# 12usb.net
KiCad netlist of a schematic drawn in EasyEDA Pro
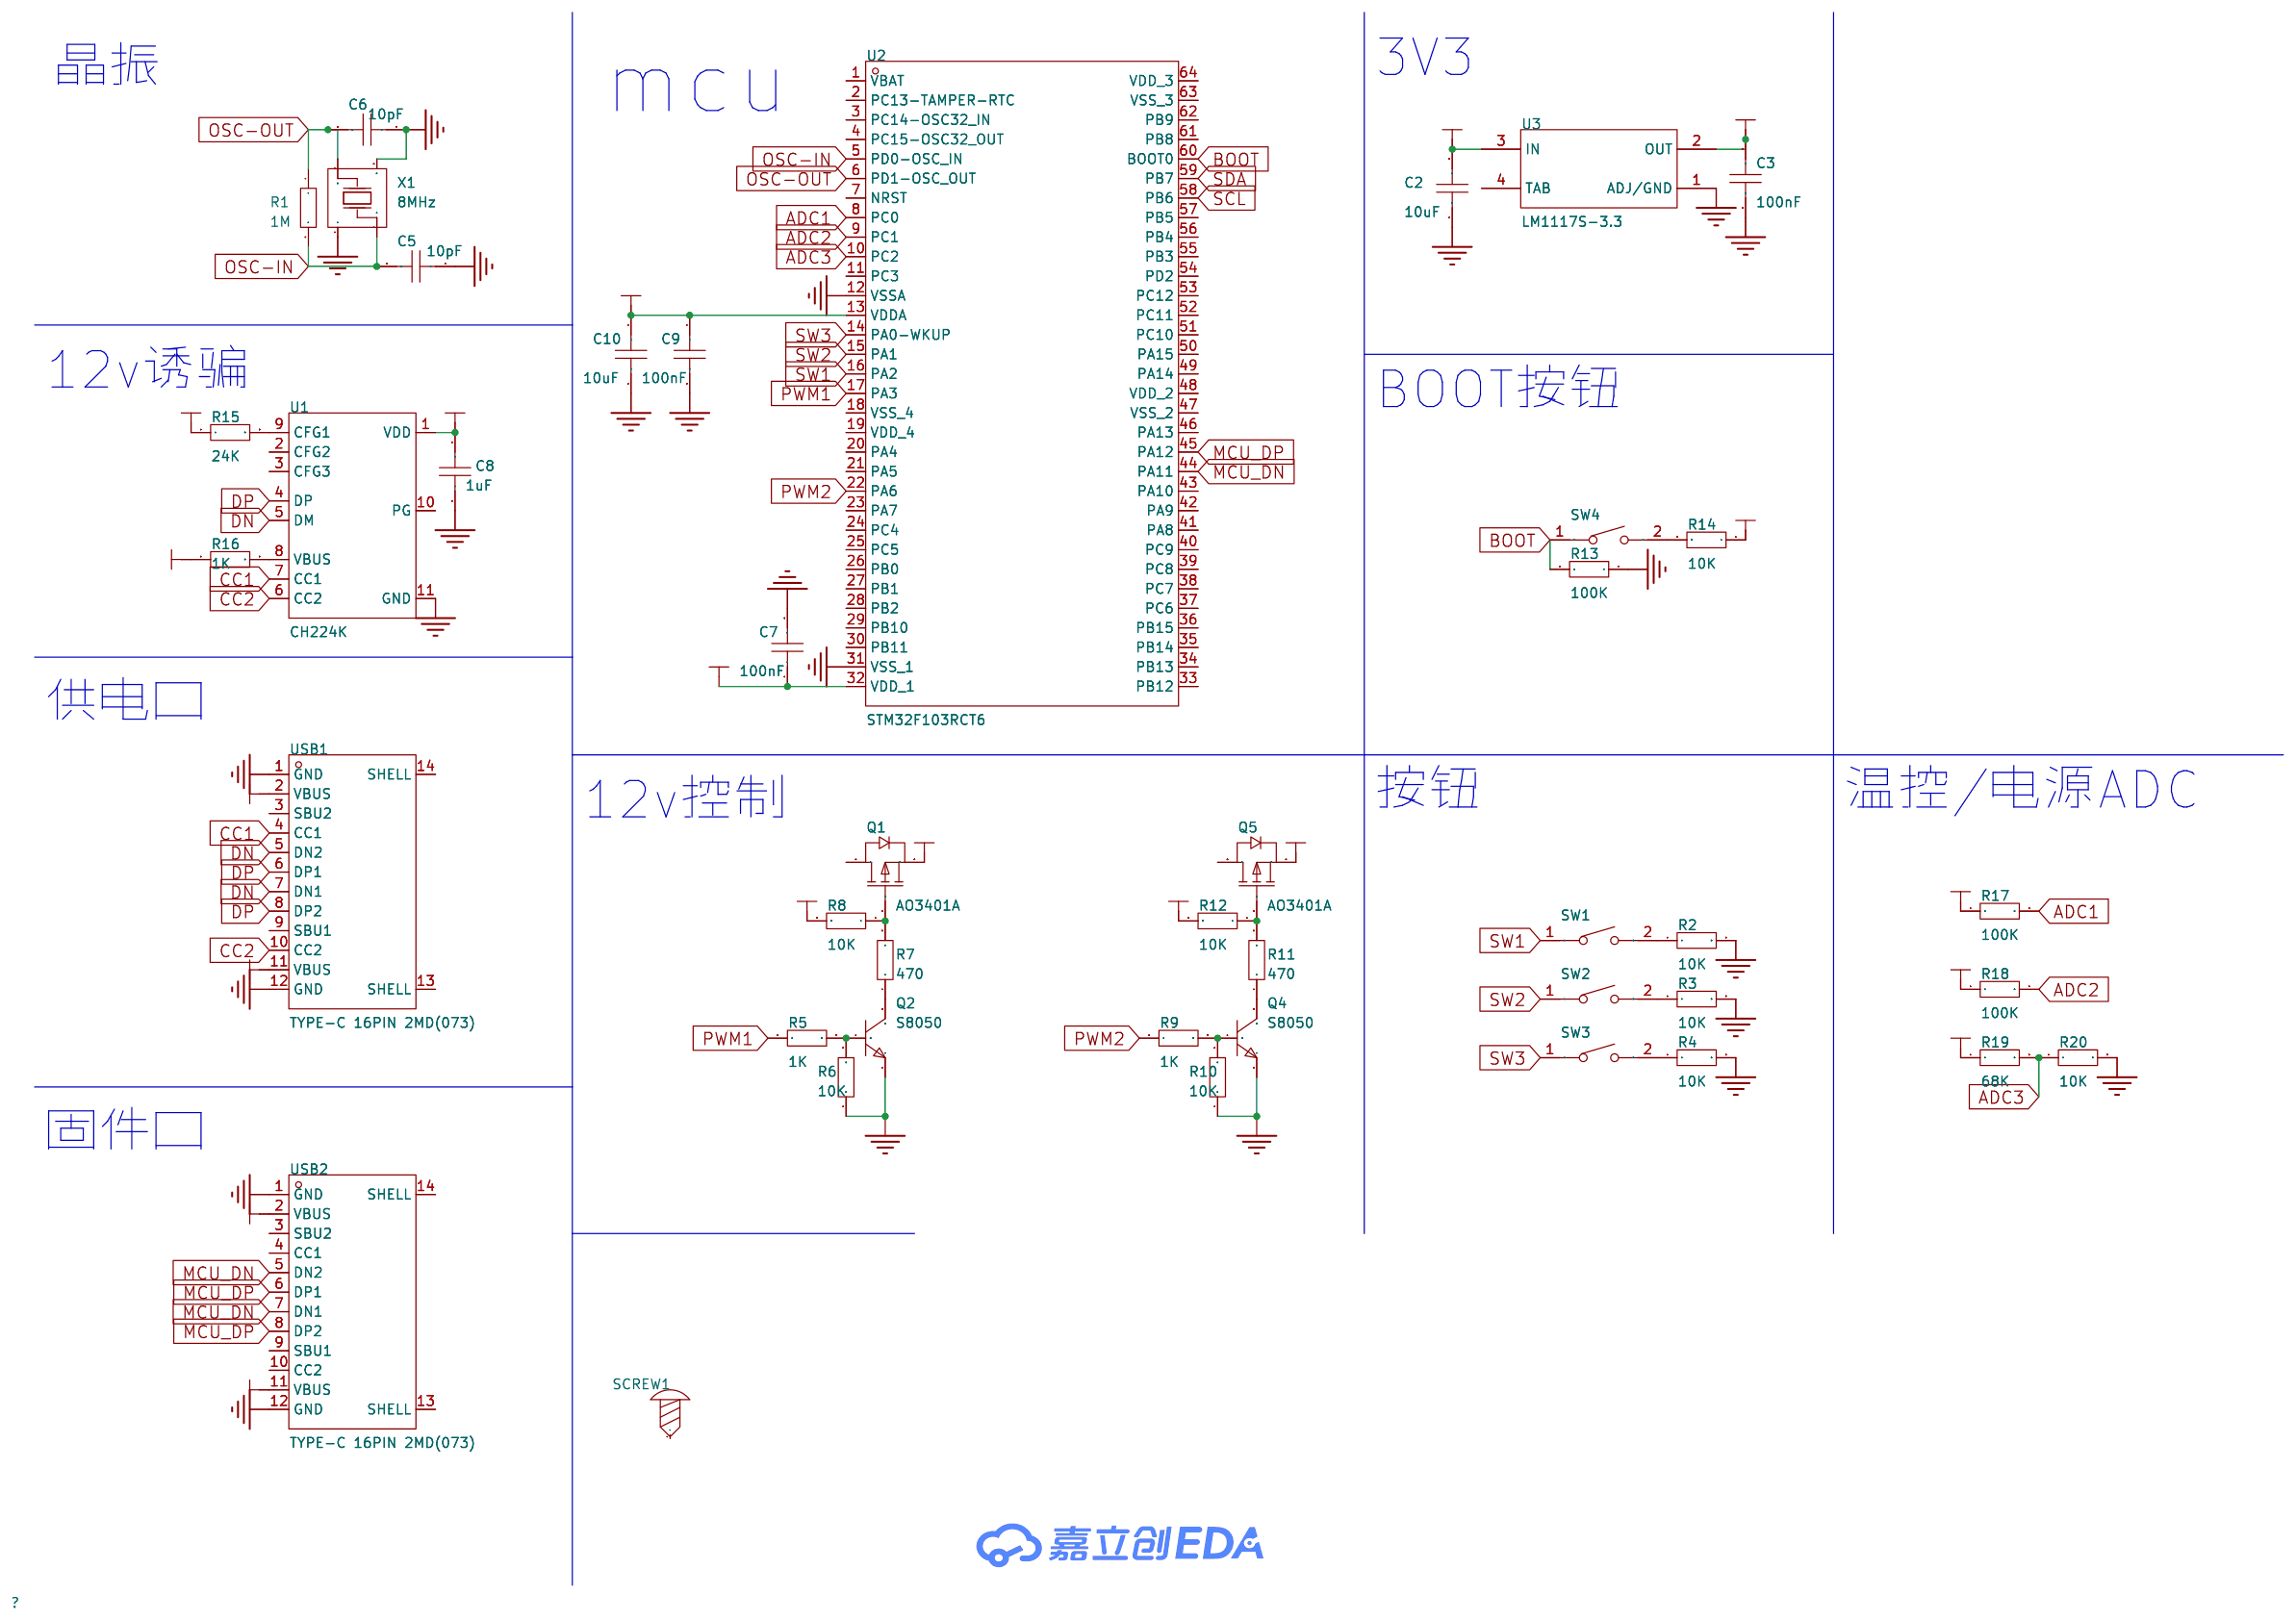
[diagram p0: schematic sheet]

(export (version "E")
  (design (tool "Eeschema 10.0.6"))
  (components
    (comp (ref "C2")
      (value "10uF")
      (footprint "easyedapro:C0603")
      (libsource (lib "easyedapro") (part "CapAcitance"))
    )
    (comp (ref "C3")
      (value "100nF")
      (footprint "easyedapro:C0603")
      (libsource (lib "easyedapro") (part "CapAcitance"))
    )
    (comp (ref "C5")
      (value "10pF")
      (footprint "easyedapro:C0603")
      (libsource (lib "easyedapro") (part "CapAcitance"))
    )
    (comp (ref "C6")
      (value "10pF")
      (footprint "easyedapro:C0603")
      (libsource (lib "easyedapro") (part "CapAcitance"))
    )
    (comp (ref "C7")
      (value "100nF")
      (footprint "easyedapro:C0603")
      (libsource (lib "easyedapro") (part "CapAcitance"))
    )
    (comp (ref "C8")
      (value "1uF")
      (footprint "easyedapro:C0603")
      (libsource (lib "easyedapro") (part "CapAcitance"))
    )
    (comp (ref "C9")
      (value "100nF")
      (footprint "easyedapro:C0603")
      (libsource (lib "easyedapro") (part "CapAcitance"))
    )
    (comp (ref "C10")
      (value "10uF")
      (footprint "easyedapro:C0603")
      (libsource (lib "easyedapro") (part "CapAcitance"))
    )
    (comp (ref "Q1")
      (value "AO3401A")
      (footprint "easyedapro:SOT-23_L2.9-W1.3-P1.90-LS2.4-BR")
      (fields (field (name "Manufacturer") "AOS"))
      (libsource (lib "easyedapro") (part "AO3401A"))
    )
    (comp (ref "Q2")
      (value "S8050")
      (footprint "easyedapro:SOT-23-3_L2.9-W1.3-P1.90-LS2.3-BR")
      (description "晶体管类型:NPN;集电极电流(Ic):500mA;集射极击穿电压(Vceo):25V;功率(Pd):300mW;直流电流增益(hFE@Ic,Vce):120@50mA,1.0V;")
      (fields (field (name "Manufacturer") "宏迦橙"))
      (libsource (lib "easyedapro") (part "S8050_C20069125"))
    )
    (comp (ref "Q4")
      (value "S8050")
      (footprint "easyedapro:SOT-23-3_L2.9-W1.3-P1.90-LS2.3-BR")
      (description "晶体管类型:NPN;集电极电流(Ic):500mA;集射极击穿电压(Vceo):25V;功率(Pd):300mW;直流电流增益(hFE@Ic,Vce):120@50mA,1.0V;")
      (fields (field (name "Manufacturer") "宏迦橙"))
      (libsource (lib "easyedapro") (part "S8050_C20069125"))
    )
    (comp (ref "Q5")
      (value "AO3401A")
      (footprint "easyedapro:SOT-23_L2.9-W1.3-P1.90-LS2.4-BR")
      (fields (field (name "Manufacturer") "AOS"))
      (libsource (lib "easyedapro") (part "AO3401A"))
    )
    (comp (ref "R1") (value "1M") (footprint "easyedapro:R0603") (libsource (lib "easyedapro") (part "电阻")))
    (comp (ref "R2") (value "10K") (footprint "easyedapro:R0603") (libsource (lib "easyedapro") (part "电阻")))
    (comp (ref "R3") (value "10K") (footprint "easyedapro:R0603") (libsource (lib "easyedapro") (part "电阻")))
    (comp (ref "R4") (value "10K") (footprint "easyedapro:R0603") (libsource (lib "easyedapro") (part "电阻")))
    (comp (ref "R5") (value "1K") (footprint "easyedapro:R0603") (libsource (lib "easyedapro") (part "电阻")))
    (comp (ref "R6") (value "10K") (footprint "easyedapro:R0603") (libsource (lib "easyedapro") (part "电阻")))
    (comp (ref "R7") (value "470") (footprint "easyedapro:R0603") (libsource (lib "easyedapro") (part "电阻")))
    (comp (ref "R8") (value "10K") (footprint "easyedapro:R0603") (libsource (lib "easyedapro") (part "电阻")))
    (comp (ref "R9") (value "1K") (footprint "easyedapro:R0603") (libsource (lib "easyedapro") (part "电阻")))
    (comp (ref "R10") (value "10K") (footprint "easyedapro:R0603") (libsource (lib "easyedapro") (part "电阻")))
    (comp (ref "R11") (value "470") (footprint "easyedapro:R0603") (libsource (lib "easyedapro") (part "电阻")))
    (comp (ref "R12") (value "10K") (footprint "easyedapro:R0603") (libsource (lib "easyedapro") (part "电阻")))
    (comp (ref "R13")
      (value "100K")
      (footprint "easyedapro:R0603")
      (libsource (lib "easyedapro") (part "电阻"))
    )
    (comp (ref "R14") (value "10K") (footprint "easyedapro:R0603") (libsource (lib "easyedapro") (part "电阻")))
    (comp (ref "R15") (value "24K") (footprint "easyedapro:R0603") (libsource (lib "easyedapro") (part "电阻")))
    (comp (ref "R16") (value "1K") (footprint "easyedapro:R0603") (libsource (lib "easyedapro") (part "电阻")))
    (comp (ref "R17")
      (value "100K")
      (footprint "easyedapro:R0603")
      (libsource (lib "easyedapro") (part "电阻"))
    )
    (comp (ref "R18")
      (value "100K")
      (footprint "easyedapro:R0603")
      (libsource (lib "easyedapro") (part "电阻"))
    )
    (comp (ref "R19") (value "68K") (footprint "easyedapro:R0603") (libsource (lib "easyedapro") (part "电阻")))
    (comp (ref "R20") (value "10K") (footprint "easyedapro:R0603") (libsource (lib "easyedapro") (part "电阻")))
    (comp (ref "SCREW1")
      (value "~")
      (footprint "easyedapro:M2螺丝")
      (libsource (lib "easyedapro") (part "螺丝孔"))
    )
    (comp (ref "SW1")
      (value "TS-1088-AR02016")
      (footprint "easyedapro:SW-SMD_L3.9-W3.0-P4.45")
      (fields (field (name "Manufacturer") "XUNPU(讯普)"))
      (libsource (lib "easyedapro") (part "TS-1088-AR02016"))
    )
    (comp (ref "SW2")
      (value "TS-1088-AR02016")
      (footprint "easyedapro:SW-SMD_L3.9-W3.0-P4.45")
      (fields (field (name "Manufacturer") "XUNPU(讯普)"))
      (libsource (lib "easyedapro") (part "TS-1088-AR02016"))
    )
    (comp (ref "SW3")
      (value "TS-1088-AR02016")
      (footprint "easyedapro:SW-SMD_L3.9-W3.0-P4.45")
      (fields (field (name "Manufacturer") "XUNPU(讯普)"))
      (libsource (lib "easyedapro") (part "TS-1088-AR02016"))
    )
    (comp (ref "SW4")
      (value "TS-1088-AR02016")
      (footprint "easyedapro:SW-SMD_L3.9-W3.0-P4.45")
      (fields (field (name "Manufacturer") "XUNPU(讯普)"))
      (libsource (lib "easyedapro") (part "TS-1088-AR02016"))
    )
    (comp (ref "U1")
      (value "CH224K")
      (footprint "easyedapro:ESSOP-10_L4.9-W3.9-P1.0-LS6.0-TL-EP")
      (fields (field (name "Manufacturer") "WCH(南京沁恒)"))
      (libsource (lib "easyedapro") (part "CH224K"))
    )
    (comp (ref "U2")
      (value "STM32F103RCT6")
      (footprint "easyedapro:LQFP-64_L10.0-W10.0-P0.50-LS12.0-BL")
      (description "CPU内核:ARM-M3;程序存储容量:256KB;RAM总容量:48KB;GPIO端口数量:51;工作电压范围:2V~3.6V;CPU最大主频:72MHz;程序存储器类型:FLASH;")
      (fields (field (name "Manufacturer") "ST(意法半导体)"))
      (libsource (lib "easyedapro") (part "STM32F103RCT6"))
    )
    (comp (ref "U3")
      (value "LM1117S-3.3")
      (footprint "easyedapro:SOT-223-3_L6.5-W3.4-P2.30-LS7.0-BR")
      (description "输出类型:固定;最大输入电压:12V;输出电压:3.3V;最大输出电流:1A;电源纹波抑制比(PSRR):75dB@(120Hz);输出极性:正极;")
      (fields (field (name "Manufacturer") "HTC"))
      (libsource (lib "easyedapro") (part "LM1117S-3.3"))
    )
    (comp (ref "USB1")
      (value "TYPE-C 16PIN 2MD(073)")
      (footprint "easyedapro:USB-C-SMD_TYPE-C-6PIN-2MD-073")
      (description "连接器类型:Type-C;标准:USB 3.1;公母:母;安装方式:卧贴;触点数量:16P;端口数量:1;额定电流 - 电源:5A;工作温度范围:-25°C~+85°C;")
      (fields (field (name "Manufacturer") "SHOU HAN(首韩)"))
      (libsource (lib "easyedapro") (part "TYPE-C 16PIN 2MD(073)"))
    )
    (comp (ref "USB2")
      (value "TYPE-C 16PIN 2MD(073)")
      (footprint "easyedapro:USB-C-SMD_TYPE-C-6PIN-2MD-073")
      (description "连接器类型:Type-C;标准:USB 3.1;公母:母;安装方式:卧贴;触点数量:16P;端口数量:1;额定电流 - 电源:5A;工作温度范围:-25°C~+85°C;")
      (fields (field (name "Manufacturer") "SHOU HAN(首韩)"))
      (libsource (lib "easyedapro") (part "TYPE-C 16PIN 2MD(073)"))
    )
    (comp (ref "X1")
      (value "8MHz")
      (footprint "easyedapro:CRYSTAL-SMD_4P-L3.2-W2.5-BL")
      (description "晶振类型:贴片晶振;频率:8MHz;常温频差:±10ppm;负载电容:10pF;频率稳定度(全温):±15ppm;")
      (fields (field (name "Manufacturer Part") "TAXM8M4RDBCCT2T") (field (name "Manufacturer") "YJX(雅晶鑫)"))
      (libsource (lib "easyedapro") (part "TAXM8M4RDBCCT2T"))
    )
  )
  (nets
    (net (code "1") (name "3V3") (class "Default")
      (node (ref "C10") (pin "1") (pinfunction "1_1") (pintype "input"))
      (node (ref "C3") (pin "2") (pinfunction "2_2") (pintype "input"))
      (node (ref "C7") (pin "1") (pinfunction "1_1") (pintype "input"))
      (node (ref "C9") (pin "1") (pinfunction "1_1") (pintype "input"))
      (node (ref "R14") (pin "1") (pinfunction "1_1") (pintype "input"))
      (node (ref "R17") (pin "1") (pinfunction "1_1") (pintype "input"))
      (node (ref "R18") (pin "1") (pinfunction "1_1") (pintype "input"))
      (node (ref "U2") (pin "13") (pinfunction "VDDA_13") (pintype "unspecified"))
      (node (ref "U2") (pin "32") (pinfunction "VDD_1_32") (pintype "unspecified"))
      (node (ref "U3") (pin "2") (pinfunction "OUT_2") (pintype "unspecified"))
    )
    (net (code "2") (name "12V") (class "Default")
      (node (ref "C2") (pin "2") (pinfunction "2_2") (pintype "input"))
      (node (ref "C8") (pin "1") (pinfunction "1_1") (pintype "input"))
      (node (ref "Q1") (pin "2") (pinfunction "S_2") (pintype "unspecified"))
      (node (ref "Q5") (pin "2") (pinfunction "S_2") (pintype "unspecified"))
      (node (ref "R12") (pin "2") (pinfunction "2_2") (pintype "input"))
      (node (ref "R15") (pin "1") (pinfunction "1_1") (pintype "input"))
      (node (ref "R16") (pin "1") (pinfunction "1_1") (pintype "input"))
      (node (ref "R19") (pin "1") (pinfunction "1_1") (pintype "input"))
      (node (ref "R8") (pin "2") (pinfunction "2_2") (pintype "input"))
      (node (ref "U1") (pin "1") (pinfunction "VDD_1") (pintype "unspecified"))
      (node (ref "U3") (pin "3") (pinfunction "IN_3") (pintype "unspecified"))
      (node (ref "USB1") (pin "11") (pinfunction "VBUS_11") (pintype "unspecified"))
      (node (ref "USB1") (pin "2") (pinfunction "VBUS_2") (pintype "unspecified"))
      (node (ref "USB2") (pin "11") (pinfunction "VBUS_11") (pintype "unspecified"))
      (node (ref "USB2") (pin "2") (pinfunction "VBUS_2") (pintype "unspecified"))
    )
    (net (code "3") (name "ADC1") (class "Default")
      (node (ref "R17") (pin "2") (pinfunction "2_2") (pintype "input"))
      (node (ref "U2") (pin "8") (pinfunction "PC0_8") (pintype "unspecified"))
    )
    (net (code "4") (name "ADC2") (class "Default")
      (node (ref "R18") (pin "2") (pinfunction "2_2") (pintype "input"))
      (node (ref "U2") (pin "9") (pinfunction "PC1_9") (pintype "unspecified"))
    )
    (net (code "5") (name "ADC3") (class "Default")
      (node (ref "R19") (pin "2") (pinfunction "2_2") (pintype "input"))
      (node (ref "R20") (pin "1") (pinfunction "1_1") (pintype "input"))
      (node (ref "U2") (pin "10") (pinfunction "PC2_10") (pintype "unspecified"))
    )
    (net (code "6") (name "BOOT") (class "Default")
      (node (ref "R13") (pin "2") (pinfunction "2_2") (pintype "input"))
      (node (ref "SW4") (pin "1") (pinfunction "1_1") (pintype "unspecified"))
      (node (ref "U2") (pin "60") (pinfunction "BOOT0_60") (pintype "unspecified"))
    )
    (net (code "7") (name "CC1") (class "Default")
      (node (ref "U1") (pin "7") (pinfunction "CC1_7") (pintype "unspecified"))
      (node (ref "USB1") (pin "4") (pinfunction "CC1_4") (pintype "unspecified"))
    )
    (net (code "8") (name "CC2") (class "Default")
      (node (ref "U1") (pin "6") (pinfunction "CC2_6") (pintype "unspecified"))
      (node (ref "USB1") (pin "10") (pinfunction "CC2_10") (pintype "unspecified"))
    )
    (net (code "9") (name "DN") (class "Default")
      (node (ref "U1") (pin "5") (pinfunction "DM_5") (pintype "unspecified"))
      (node (ref "USB1") (pin "5") (pinfunction "DN2_5") (pintype "unspecified"))
      (node (ref "USB1") (pin "7") (pinfunction "DN1_7") (pintype "unspecified"))
    )
    (net (code "10") (name "DP") (class "Default")
      (node (ref "U1") (pin "4") (pinfunction "DP_4") (pintype "unspecified"))
      (node (ref "USB1") (pin "6") (pinfunction "DP1_6") (pintype "unspecified"))
      (node (ref "USB1") (pin "8") (pinfunction "DP2_8") (pintype "unspecified"))
    )
    (net (code "11") (name "GND") (class "Default")
      (node (ref "C10") (pin "2") (pinfunction "2_2") (pintype "input"))
      (node (ref "C2") (pin "1") (pinfunction "1_1") (pintype "input"))
      (node (ref "C3") (pin "1") (pinfunction "1_1") (pintype "input"))
      (node (ref "C5") (pin "1") (pinfunction "1_1") (pintype "input"))
      (node (ref "C6") (pin "1") (pinfunction "1_1") (pintype "input"))
      (node (ref "C7") (pin "2") (pinfunction "2_2") (pintype "input"))
      (node (ref "C8") (pin "2") (pinfunction "2_2") (pintype "input"))
      (node (ref "C9") (pin "2") (pinfunction "2_2") (pintype "input"))
      (node (ref "Q2") (pin "2") (pinfunction "E_2") (pintype "input"))
      (node (ref "Q4") (pin "2") (pinfunction "E_2") (pintype "input"))
      (node (ref "R10") (pin "1") (pinfunction "1_1") (pintype "input"))
      (node (ref "R13") (pin "1") (pinfunction "1_1") (pintype "input"))
      (node (ref "R2") (pin "2") (pinfunction "2_2") (pintype "input"))
      (node (ref "R20") (pin "2") (pinfunction "2_2") (pintype "input"))
      (node (ref "R3") (pin "2") (pinfunction "2_2") (pintype "input"))
      (node (ref "R4") (pin "2") (pinfunction "2_2") (pintype "input"))
      (node (ref "R6") (pin "1") (pinfunction "1_1") (pintype "input"))
      (node (ref "U1") (pin "11") (pinfunction "GND_11") (pintype "unspecified"))
      (node (ref "U2") (pin "12") (pinfunction "VSSA_12") (pintype "unspecified"))
      (node (ref "U2") (pin "31") (pinfunction "VSS_1_31") (pintype "unspecified"))
      (node (ref "U3") (pin "1") (pinfunction "ADJ/GND_1") (pintype "unspecified"))
      (node (ref "USB1") (pin "1") (pinfunction "GND_1") (pintype "unspecified"))
      (node (ref "USB1") (pin "12") (pinfunction "GND_12") (pintype "unspecified"))
      (node (ref "USB2") (pin "1") (pinfunction "GND_1") (pintype "unspecified"))
      (node (ref "USB2") (pin "12") (pinfunction "GND_12") (pintype "unspecified"))
      (node (ref "X1") (pin "2") (pinfunction "2_2") (pintype "input"))
      (node (ref "X1") (pin "4") (pinfunction "4_4") (pintype "input"))
    )
    (net (code "12") (name "MCU_DN") (class "Default")
      (node (ref "U2") (pin "44") (pinfunction "PA11_44") (pintype "unspecified"))
      (node (ref "USB2") (pin "5") (pinfunction "DN2_5") (pintype "unspecified"))
      (node (ref "USB2") (pin "7") (pinfunction "DN1_7") (pintype "unspecified"))
    )
    (net (code "13") (name "MCU_DP") (class "Default")
      (node (ref "U2") (pin "45") (pinfunction "PA12_45") (pintype "unspecified"))
      (node (ref "USB2") (pin "6") (pinfunction "DP1_6") (pintype "unspecified"))
      (node (ref "USB2") (pin "8") (pinfunction "DP2_8") (pintype "unspecified"))
    )
    (net (code "14") (name "Net-(Q1-G)") (class "Default")
      (node (ref "Q1") (pin "1") (pinfunction "G_1") (pintype "unspecified"))
      (node (ref "R7") (pin "2") (pinfunction "2_2") (pintype "input"))
      (node (ref "R8") (pin "1") (pinfunction "1_1") (pintype "input"))
    )
    (net (code "15") (name "Net-(Q2-B)") (class "Default")
      (node (ref "Q2") (pin "1") (pinfunction "B_1") (pintype "input"))
      (node (ref "R5") (pin "2") (pinfunction "2_2") (pintype "input"))
      (node (ref "R6") (pin "2") (pinfunction "2_2") (pintype "input"))
    )
    (net (code "16") (name "Net-(Q2-C)") (class "Default")
      (node (ref "Q2") (pin "3") (pinfunction "C_3") (pintype "input"))
      (node (ref "R7") (pin "1") (pinfunction "1_1") (pintype "input"))
    )
    (net (code "17") (name "Net-(Q4-B)") (class "Default")
      (node (ref "Q4") (pin "1") (pinfunction "B_1") (pintype "input"))
      (node (ref "R10") (pin "2") (pinfunction "2_2") (pintype "input"))
      (node (ref "R9") (pin "2") (pinfunction "2_2") (pintype "input"))
    )
    (net (code "18") (name "Net-(Q4-C)") (class "Default")
      (node (ref "Q4") (pin "3") (pinfunction "C_3") (pintype "input"))
      (node (ref "R11") (pin "1") (pinfunction "1_1") (pintype "input"))
    )
    (net (code "19") (name "Net-(Q5-G)") (class "Default")
      (node (ref "Q5") (pin "1") (pinfunction "G_1") (pintype "unspecified"))
      (node (ref "R11") (pin "2") (pinfunction "2_2") (pintype "input"))
      (node (ref "R12") (pin "1") (pinfunction "1_1") (pintype "input"))
    )
    (net (code "20") (name "Net-(R2-Pad1)") (class "Default")
      (node (ref "R2") (pin "1") (pinfunction "1_1") (pintype "input"))
      (node (ref "SW1") (pin "2") (pinfunction "2_2") (pintype "unspecified"))
    )
    (net (code "21") (name "Net-(R3-Pad1)") (class "Default")
      (node (ref "R3") (pin "1") (pinfunction "1_1") (pintype "input"))
      (node (ref "SW2") (pin "2") (pinfunction "2_2") (pintype "unspecified"))
    )
    (net (code "22") (name "Net-(R4-Pad1)") (class "Default")
      (node (ref "R4") (pin "1") (pinfunction "1_1") (pintype "input"))
      (node (ref "SW3") (pin "2") (pinfunction "2_2") (pintype "unspecified"))
    )
    (net (code "23") (name "Net-(R14-Pad2)") (class "Default")
      (node (ref "R14") (pin "2") (pinfunction "2_2") (pintype "input"))
      (node (ref "SW4") (pin "2") (pinfunction "2_2") (pintype "unspecified"))
    )
    (net (code "24") (name "Net-(U1-CFG1)") (class "Default")
      (node (ref "R15") (pin "2") (pinfunction "2_2") (pintype "input"))
      (node (ref "U1") (pin "9") (pinfunction "CFG1_9") (pintype "unspecified"))
    )
    (net (code "25") (name "Net-(U1-VBUS)") (class "Default")
      (node (ref "R16") (pin "2") (pinfunction "2_2") (pintype "input"))
      (node (ref "U1") (pin "8") (pinfunction "VBUS_8") (pintype "unspecified"))
    )
    (net (code "26") (name "OSC-IN") (class "Default")
      (node (ref "C5") (pin "2") (pinfunction "2_2") (pintype "input"))
      (node (ref "R1") (pin "2") (pinfunction "2_2") (pintype "input"))
      (node (ref "U2") (pin "5") (pinfunction "PD0-OSC_IN_5") (pintype "unspecified"))
      (node (ref "X1") (pin "1") (pinfunction "1_1") (pintype "input"))
    )
    (net (code "27") (name "OSC-OUT") (class "Default")
      (node (ref "C6") (pin "2") (pinfunction "2_2") (pintype "input"))
      (node (ref "R1") (pin "1") (pinfunction "1_1") (pintype "input"))
      (node (ref "U2") (pin "6") (pinfunction "PD1-OSC_OUT_6") (pintype "unspecified"))
      (node (ref "X1") (pin "3") (pinfunction "3_3") (pintype "input"))
    )
    (net (code "28") (name "PWM1") (class "Default")
      (node (ref "R5") (pin "1") (pinfunction "1_1") (pintype "input"))
      (node (ref "U2") (pin "17") (pinfunction "PA3_17") (pintype "unspecified"))
    )
    (net (code "29") (name "PWM2") (class "Default")
      (node (ref "R9") (pin "1") (pinfunction "1_1") (pintype "input"))
      (node (ref "U2") (pin "22") (pinfunction "PA6_22") (pintype "unspecified"))
    )
    (net (code "30") (name "SCL") (class "Default")
      (node (ref "U2") (pin "58") (pinfunction "PB6_58") (pintype "unspecified"))
    )
    (net (code "31") (name "SDA") (class "Default")
      (node (ref "U2") (pin "59") (pinfunction "PB7_59") (pintype "unspecified"))
    )
    (net (code "32") (name "SW1") (class "Default")
      (node (ref "SW1") (pin "1") (pinfunction "1_1") (pintype "unspecified"))
      (node (ref "U2") (pin "16") (pinfunction "PA2_16") (pintype "unspecified"))
    )
    (net (code "33") (name "SW2") (class "Default")
      (node (ref "SW2") (pin "1") (pinfunction "1_1") (pintype "unspecified"))
      (node (ref "U2") (pin "15") (pinfunction "PA1_15") (pintype "unspecified"))
    )
    (net (code "34") (name "SW3") (class "Default")
      (node (ref "SW3") (pin "1") (pinfunction "1_1") (pintype "unspecified"))
      (node (ref "U2") (pin "14") (pinfunction "PA0-WKUP_14") (pintype "unspecified"))
    )
    (net (code "35") (name "unconnected-(Q1-D-Pad3)") (class "Default")
      (node (ref "Q1") (pin "3") (pinfunction "D_3") (pintype "unspecified"))
    )
    (net (code "36") (name "unconnected-(Q5-D-Pad3)") (class "Default")
      (node (ref "Q5") (pin "3") (pinfunction "D_3") (pintype "unspecified"))
    )
    (net (code "37") (name "unconnected-(SCREW1-Pad1)") (class "Default")
      (node (ref "SCREW1") (pin "1") (pinfunction "1_1") (pintype "input"))
    )
    (net (code "38") (name "unconnected-(U1-CFG2-Pad2)") (class "Default")
      (node (ref "U1") (pin "2") (pinfunction "CFG2_2") (pintype "unspecified"))
    )
    (net (code "39") (name "unconnected-(U1-CFG3-Pad3)") (class "Default")
      (node (ref "U1") (pin "3") (pinfunction "CFG3_3") (pintype "unspecified"))
    )
    (net (code "40") (name "unconnected-(U1-PG-Pad10)") (class "Default")
      (node (ref "U1") (pin "10") (pinfunction "PG_10") (pintype "unspecified"))
    )
    (net (code "41") (name "unconnected-(U2-NRST-Pad7)") (class "Default")
      (node (ref "U2") (pin "7") (pinfunction "NRST_7") (pintype "unspecified"))
    )
    (net (code "42") (name "unconnected-(U2-PA4-Pad20)") (class "Default")
      (node (ref "U2") (pin "20") (pinfunction "PA4_20") (pintype "unspecified"))
    )
    (net (code "43") (name "unconnected-(U2-PA5-Pad21)") (class "Default")
      (node (ref "U2") (pin "21") (pinfunction "PA5_21") (pintype "unspecified"))
    )
    (net (code "44") (name "unconnected-(U2-PA7-Pad23)") (class "Default")
      (node (ref "U2") (pin "23") (pinfunction "PA7_23") (pintype "unspecified"))
    )
    (net (code "45") (name "unconnected-(U2-PA8-Pad41)") (class "Default")
      (node (ref "U2") (pin "41") (pinfunction "PA8_41") (pintype "unspecified"))
    )
    (net (code "46") (name "unconnected-(U2-PA9-Pad42)") (class "Default")
      (node (ref "U2") (pin "42") (pinfunction "PA9_42") (pintype "unspecified"))
    )
    (net (code "47") (name "unconnected-(U2-PA10-Pad43)") (class "Default")
      (node (ref "U2") (pin "43") (pinfunction "PA10_43") (pintype "unspecified"))
    )
    (net (code "48") (name "unconnected-(U2-PA13-Pad46)") (class "Default")
      (node (ref "U2") (pin "46") (pinfunction "PA13_46") (pintype "unspecified"))
    )
    (net (code "49") (name "unconnected-(U2-PA14-Pad49)") (class "Default")
      (node (ref "U2") (pin "49") (pinfunction "PA14_49") (pintype "unspecified"))
    )
    (net (code "50") (name "unconnected-(U2-PA15-Pad50)") (class "Default")
      (node (ref "U2") (pin "50") (pinfunction "PA15_50") (pintype "unspecified"))
    )
    (net (code "51") (name "unconnected-(U2-PB0-Pad26)") (class "Default")
      (node (ref "U2") (pin "26") (pinfunction "PB0_26") (pintype "unspecified"))
    )
    (net (code "52") (name "unconnected-(U2-PB1-Pad27)") (class "Default")
      (node (ref "U2") (pin "27") (pinfunction "PB1_27") (pintype "unspecified"))
    )
    (net (code "53") (name "unconnected-(U2-PB2-Pad28)") (class "Default")
      (node (ref "U2") (pin "28") (pinfunction "PB2_28") (pintype "unspecified"))
    )
    (net (code "54") (name "unconnected-(U2-PB3-Pad55)") (class "Default")
      (node (ref "U2") (pin "55") (pinfunction "PB3_55") (pintype "unspecified"))
    )
    (net (code "55") (name "unconnected-(U2-PB4-Pad56)") (class "Default")
      (node (ref "U2") (pin "56") (pinfunction "PB4_56") (pintype "unspecified"))
    )
    (net (code "56") (name "unconnected-(U2-PB5-Pad57)") (class "Default")
      (node (ref "U2") (pin "57") (pinfunction "PB5_57") (pintype "unspecified"))
    )
    (net (code "57") (name "unconnected-(U2-PB8-Pad61)") (class "Default")
      (node (ref "U2") (pin "61") (pinfunction "PB8_61") (pintype "unspecified"))
    )
    (net (code "58") (name "unconnected-(U2-PB9-Pad62)") (class "Default")
      (node (ref "U2") (pin "62") (pinfunction "PB9_62") (pintype "unspecified"))
    )
    (net (code "59") (name "unconnected-(U2-PB10-Pad29)") (class "Default")
      (node (ref "U2") (pin "29") (pinfunction "PB10_29") (pintype "unspecified"))
    )
    (net (code "60") (name "unconnected-(U2-PB11-Pad30)") (class "Default")
      (node (ref "U2") (pin "30") (pinfunction "PB11_30") (pintype "unspecified"))
    )
    (net (code "61") (name "unconnected-(U2-PB12-Pad33)") (class "Default")
      (node (ref "U2") (pin "33") (pinfunction "PB12_33") (pintype "unspecified"))
    )
    (net (code "62") (name "unconnected-(U2-PB13-Pad34)") (class "Default")
      (node (ref "U2") (pin "34") (pinfunction "PB13_34") (pintype "unspecified"))
    )
    (net (code "63") (name "unconnected-(U2-PB14-Pad35)") (class "Default")
      (node (ref "U2") (pin "35") (pinfunction "PB14_35") (pintype "unspecified"))
    )
    (net (code "64") (name "unconnected-(U2-PB15-Pad36)") (class "Default")
      (node (ref "U2") (pin "36") (pinfunction "PB15_36") (pintype "unspecified"))
    )
    (net (code "65") (name "unconnected-(U2-PC3-Pad11)") (class "Default")
      (node (ref "U2") (pin "11") (pinfunction "PC3_11") (pintype "unspecified"))
    )
    (net (code "66") (name "unconnected-(U2-PC4-Pad24)") (class "Default")
      (node (ref "U2") (pin "24") (pinfunction "PC4_24") (pintype "unspecified"))
    )
    (net (code "67") (name "unconnected-(U2-PC5-Pad25)") (class "Default")
      (node (ref "U2") (pin "25") (pinfunction "PC5_25") (pintype "unspecified"))
    )
    (net (code "68") (name "unconnected-(U2-PC6-Pad37)") (class "Default")
      (node (ref "U2") (pin "37") (pinfunction "PC6_37") (pintype "unspecified"))
    )
    (net (code "69") (name "unconnected-(U2-PC7-Pad38)") (class "Default")
      (node (ref "U2") (pin "38") (pinfunction "PC7_38") (pintype "unspecified"))
    )
    (net (code "70") (name "unconnected-(U2-PC8-Pad39)") (class "Default")
      (node (ref "U2") (pin "39") (pinfunction "PC8_39") (pintype "unspecified"))
    )
    (net (code "71") (name "unconnected-(U2-PC9-Pad40)") (class "Default")
      (node (ref "U2") (pin "40") (pinfunction "PC9_40") (pintype "unspecified"))
    )
    (net (code "72") (name "unconnected-(U2-PC10-Pad51)") (class "Default")
      (node (ref "U2") (pin "51") (pinfunction "PC10_51") (pintype "unspecified"))
    )
    (net (code "73") (name "unconnected-(U2-PC11-Pad52)") (class "Default")
      (node (ref "U2") (pin "52") (pinfunction "PC11_52") (pintype "unspecified"))
    )
    (net (code "74") (name "unconnected-(U2-PC12-Pad53)") (class "Default")
      (node (ref "U2") (pin "53") (pinfunction "PC12_53") (pintype "unspecified"))
    )
    (net (code "75") (name "unconnected-(U2-PC13-TAMPER-RTC-Pad2)") (class "Default")
      (node (ref "U2") (pin "2") (pinfunction "PC13-TAMPER-RTC_2") (pintype "unspecified"))
    )
    (net (code "76") (name "unconnected-(U2-PC14-OSC32_IN-Pad3)") (class "Default")
      (node (ref "U2") (pin "3") (pinfunction "PC14-OSC32_IN_3") (pintype "unspecified"))
    )
    (net (code "77") (name "unconnected-(U2-PC15-OSC32_OUT-Pad4)") (class "Default")
      (node (ref "U2") (pin "4") (pinfunction "PC15-OSC32_OUT_4") (pintype "unspecified"))
    )
    (net (code "78") (name "unconnected-(U2-PD2-Pad54)") (class "Default")
      (node (ref "U2") (pin "54") (pinfunction "PD2_54") (pintype "unspecified"))
    )
    (net (code "79") (name "unconnected-(U2-VBAT-Pad1)") (class "Default")
      (node (ref "U2") (pin "1") (pinfunction "VBAT_1") (pintype "unspecified"))
    )
    (net (code "80") (name "unconnected-(U2-VDD_2-Pad48)") (class "Default")
      (node (ref "U2") (pin "48") (pinfunction "VDD_2_48") (pintype "unspecified"))
    )
    (net (code "81") (name "unconnected-(U2-VDD_3-Pad64)") (class "Default")
      (node (ref "U2") (pin "64") (pinfunction "VDD_3_64") (pintype "unspecified"))
    )
    (net (code "82") (name "unconnected-(U2-VDD_4-Pad19)") (class "Default")
      (node (ref "U2") (pin "19") (pinfunction "VDD_4_19") (pintype "unspecified"))
    )
    (net (code "83") (name "unconnected-(U2-VSS_2-Pad47)") (class "Default")
      (node (ref "U2") (pin "47") (pinfunction "VSS_2_47") (pintype "unspecified"))
    )
    (net (code "84") (name "unconnected-(U2-VSS_3-Pad63)") (class "Default")
      (node (ref "U2") (pin "63") (pinfunction "VSS_3_63") (pintype "unspecified"))
    )
    (net (code "85") (name "unconnected-(U2-VSS_4-Pad18)") (class "Default")
      (node (ref "U2") (pin "18") (pinfunction "VSS_4_18") (pintype "unspecified"))
    )
    (net (code "86") (name "unconnected-(U3-TAB-Pad4)") (class "Default")
      (node (ref "U3") (pin "4") (pinfunction "TAB_4") (pintype "unspecified"))
    )
    (net (code "87") (name "unconnected-(USB1-SBU1-Pad9)") (class "Default")
      (node (ref "USB1") (pin "9") (pinfunction "SBU1_9") (pintype "unspecified"))
    )
    (net (code "88") (name "unconnected-(USB1-SBU2-Pad3)") (class "Default")
      (node (ref "USB1") (pin "3") (pinfunction "SBU2_3") (pintype "unspecified"))
    )
    (net (code "89") (name "unconnected-(USB1-SHELL-Pad13)") (class "Default")
      (node (ref "USB1") (pin "13") (pinfunction "SHELL_13") (pintype "unspecified"))
    )
    (net (code "90") (name "unconnected-(USB1-SHELL-Pad14)") (class "Default")
      (node (ref "USB1") (pin "14") (pinfunction "SHELL_14") (pintype "unspecified"))
    )
    (net (code "91") (name "unconnected-(USB2-CC1-Pad4)") (class "Default")
      (node (ref "USB2") (pin "4") (pinfunction "CC1_4") (pintype "unspecified"))
    )
    (net (code "92") (name "unconnected-(USB2-CC2-Pad10)") (class "Default")
      (node (ref "USB2") (pin "10") (pinfunction "CC2_10") (pintype "unspecified"))
    )
    (net (code "93") (name "unconnected-(USB2-SBU1-Pad9)") (class "Default")
      (node (ref "USB2") (pin "9") (pinfunction "SBU1_9") (pintype "unspecified"))
    )
    (net (code "94") (name "unconnected-(USB2-SBU2-Pad3)") (class "Default")
      (node (ref "USB2") (pin "3") (pinfunction "SBU2_3") (pintype "unspecified"))
    )
    (net (code "95") (name "unconnected-(USB2-SHELL-Pad13)") (class "Default")
      (node (ref "USB2") (pin "13") (pinfunction "SHELL_13") (pintype "unspecified"))
    )
    (net (code "96") (name "unconnected-(USB2-SHELL-Pad14)") (class "Default")
      (node (ref "USB2") (pin "14") (pinfunction "SHELL_14") (pintype "unspecified"))
    )
  )
)
